# SMPS_Template.net
KiCad netlist of a schematic drawn in Altium Designer
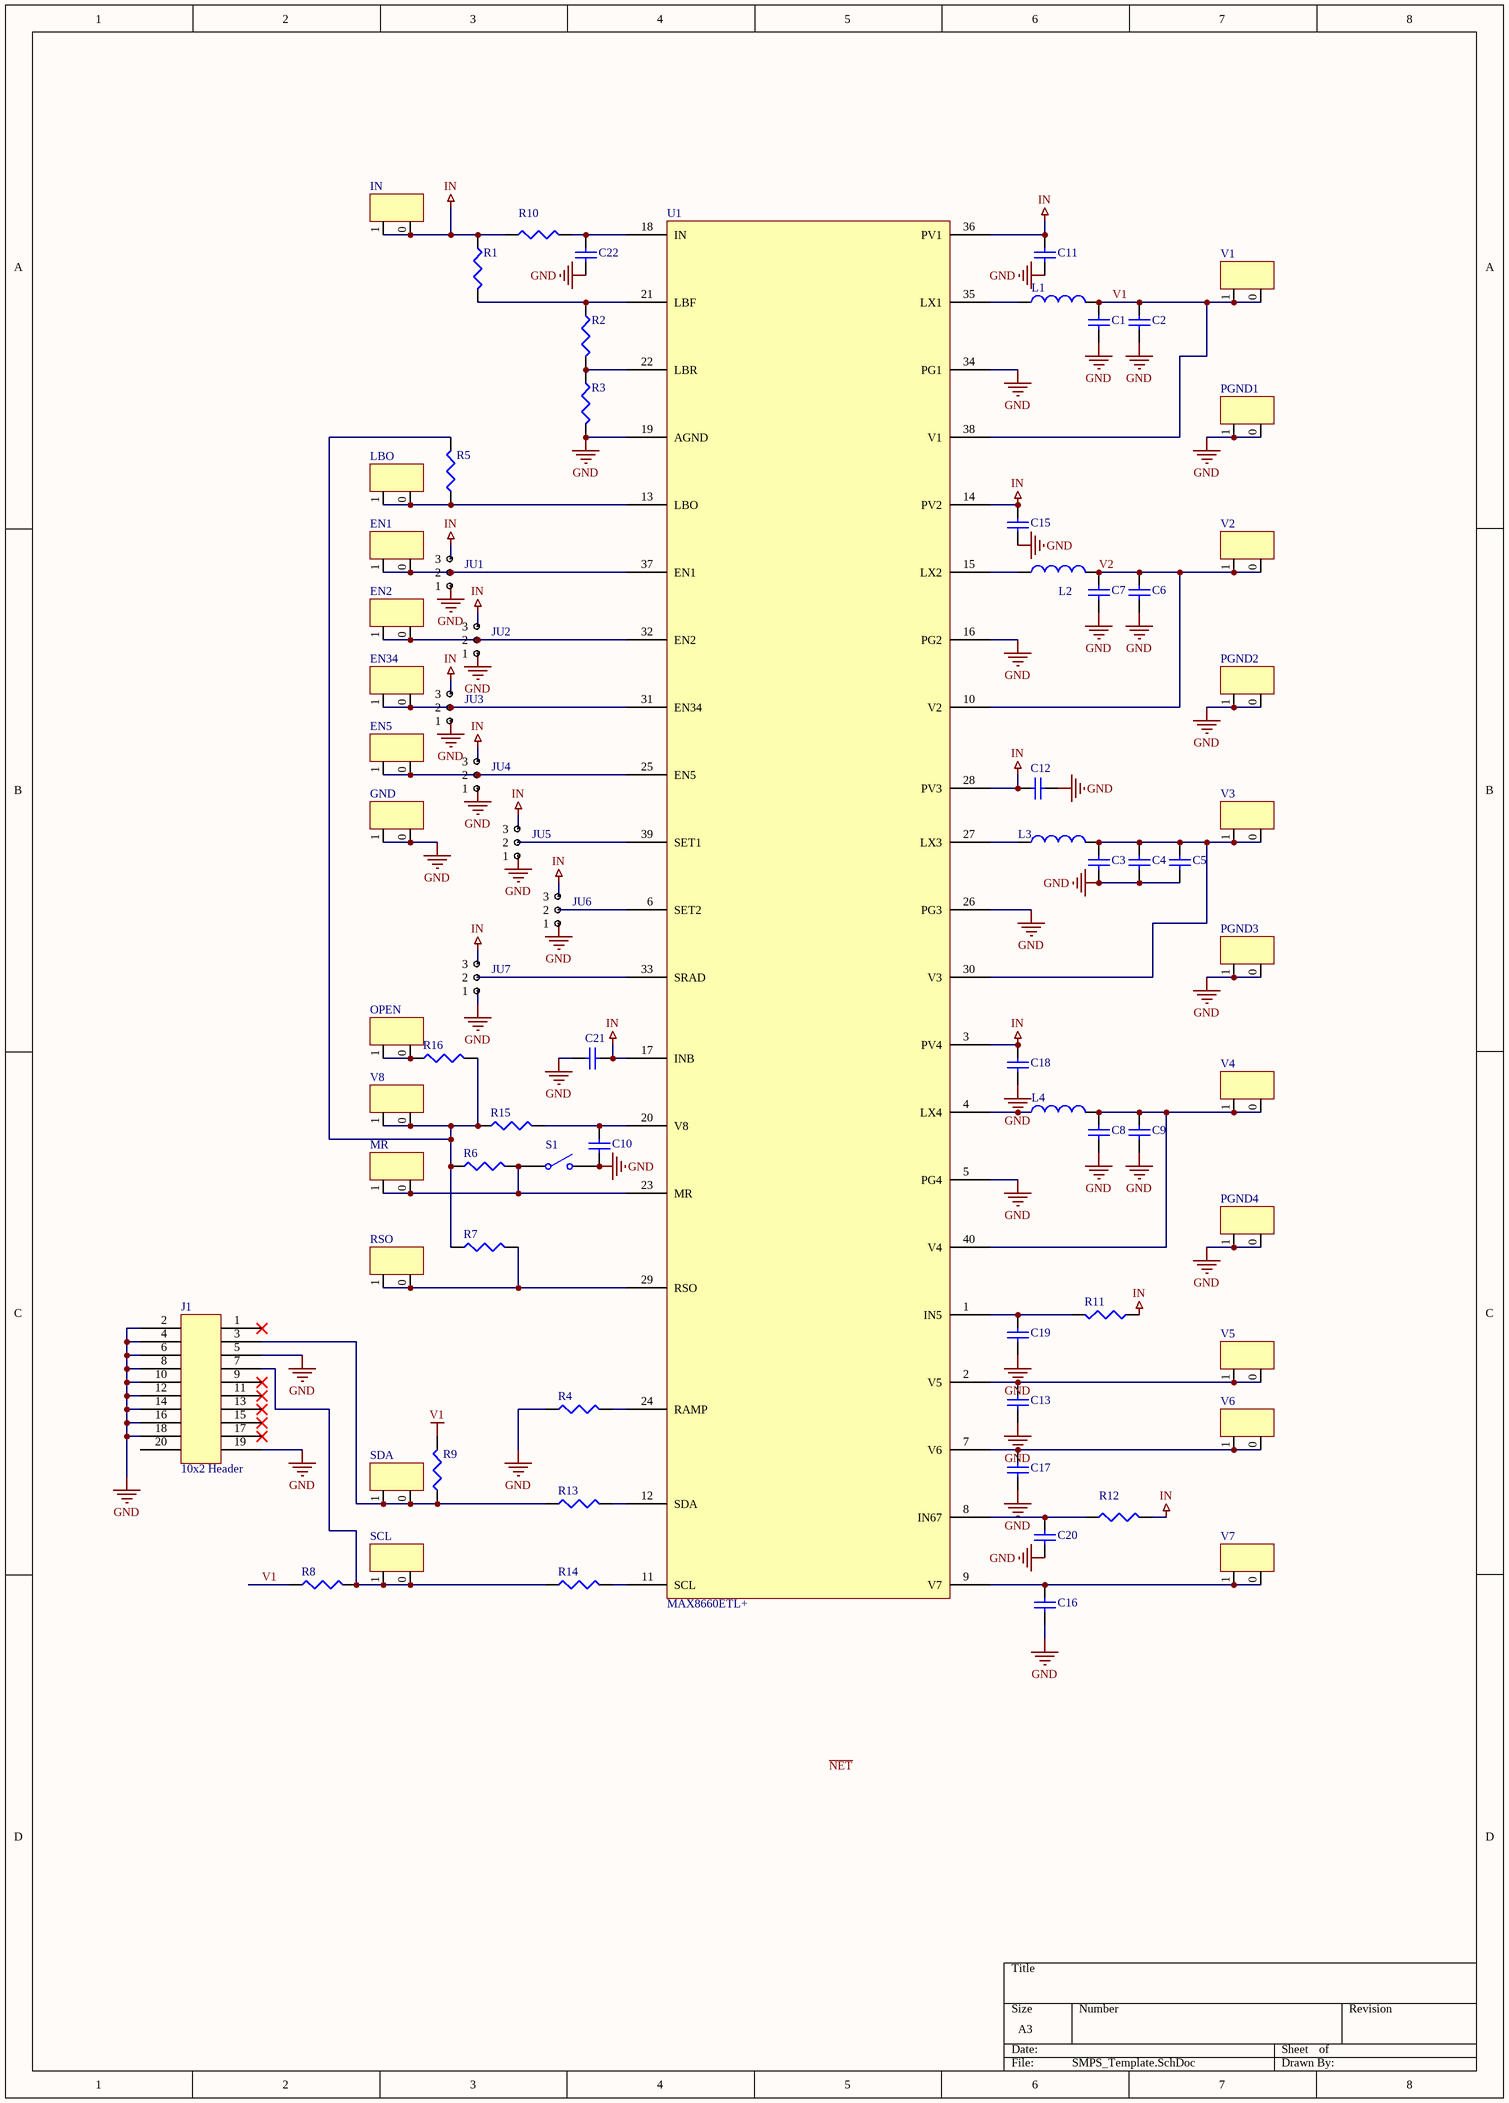
[diagram p0: SMPS_Template.SchDoc]

(export (version "E")
  (design (tool "Eeschema 10.0.6"))
  (components
    (comp (ref "C1")
      (value "Cap")
      (footprint "2012[0805]")
      (description "Capacitor")
      (fields (field (name "PUBLISHER") "Altium Limited"))
      (libsource (lib "Miscellaneous Devices") (part "Cap"))
    )
    (comp (ref "C2")
      (value "Cap")
      (footprint "2012[0805]")
      (description "Capacitor")
      (fields (field (name "PUBLISHER") "Altium Limited"))
      (libsource (lib "Miscellaneous Devices") (part "Cap"))
    )
    (comp (ref "C3")
      (value "Cap")
      (footprint "2012[0805]")
      (description "Capacitor")
      (fields (field (name "PUBLISHER") "Altium Limited"))
      (libsource (lib "Miscellaneous Devices") (part "Cap"))
    )
    (comp (ref "C4")
      (value "Cap")
      (footprint "2012[0805]")
      (description "Capacitor")
      (fields (field (name "PUBLISHER") "Altium Limited"))
      (libsource (lib "Miscellaneous Devices") (part "Cap"))
    )
    (comp (ref "C5")
      (value "Cap")
      (footprint "2012[0805]")
      (description "Capacitor")
      (fields (field (name "PUBLISHER") "Altium Limited"))
      (libsource (lib "Miscellaneous Devices") (part "Cap"))
    )
    (comp (ref "C6")
      (value "Cap")
      (footprint "2012[0805]")
      (description "Capacitor")
      (fields (field (name "PUBLISHER") "Altium Limited"))
      (libsource (lib "Miscellaneous Devices") (part "Cap"))
    )
    (comp (ref "C7")
      (value "Cap")
      (footprint "2012[0805]")
      (description "Capacitor")
      (fields (field (name "PUBLISHER") "Altium Limited"))
      (libsource (lib "Miscellaneous Devices") (part "Cap"))
    )
    (comp (ref "C8")
      (value "Cap")
      (footprint "2012[0805]")
      (description "Capacitor")
      (fields (field (name "PUBLISHER") "Altium Limited"))
      (libsource (lib "Miscellaneous Devices") (part "Cap"))
    )
    (comp (ref "C9")
      (value "Cap")
      (footprint "2012[0805]")
      (description "Capacitor")
      (fields (field (name "PUBLISHER") "Altium Limited"))
      (libsource (lib "Miscellaneous Devices") (part "Cap"))
    )
    (comp (ref "C10")
      (value "Cap")
      (footprint "1005[0402]")
      (description "Capacitor")
      (fields (field (name "PUBLISHER") "Altium Limited"))
      (libsource (lib "Miscellaneous Devices") (part "Cap"))
    )
    (comp (ref "C11")
      (value "Cap")
      (footprint "1608[0603]")
      (description "Capacitor")
      (fields (field (name "PUBLISHER") "Altium Limited"))
      (libsource (lib "Miscellaneous Devices") (part "Cap"))
    )
    (comp (ref "C12")
      (value "Cap")
      (footprint "1608[0603]")
      (description "Capacitor")
      (fields (field (name "PUBLISHER") "Altium Limited"))
      (libsource (lib "Miscellaneous Devices") (part "Cap"))
    )
    (comp (ref "C13")
      (value "Cap")
      (footprint "1608[0603]")
      (description "Capacitor")
      (fields (field (name "PUBLISHER") "Altium Limited"))
      (libsource (lib "Miscellaneous Devices") (part "Cap"))
    )
    (comp (ref "C15")
      (value "Cap")
      (footprint "1608[0603]")
      (description "Capacitor")
      (fields (field (name "PUBLISHER") "Altium Limited"))
      (libsource (lib "Miscellaneous Devices") (part "Cap"))
    )
    (comp (ref "C16")
      (value "Cap")
      (footprint "1608[0603]")
      (description "Capacitor")
      (fields (field (name "PUBLISHER") "Altium Limited"))
      (libsource (lib "Miscellaneous Devices") (part "Cap"))
    )
    (comp (ref "C17")
      (value "Cap")
      (footprint "1608[0603]")
      (description "Capacitor")
      (fields (field (name "PUBLISHER") "Altium Limited"))
      (libsource (lib "Miscellaneous Devices") (part "Cap"))
    )
    (comp (ref "C18")
      (value "Cap")
      (footprint "1608[0603]")
      (description "Capacitor")
      (fields (field (name "PUBLISHER") "Altium Limited"))
      (libsource (lib "Miscellaneous Devices") (part "Cap"))
    )
    (comp (ref "C19")
      (value "Cap")
      (footprint "1608[0603]")
      (description "Capacitor")
      (fields (field (name "PUBLISHER") "Altium Limited"))
      (libsource (lib "Miscellaneous Devices") (part "Cap"))
    )
    (comp (ref "C20")
      (value "Cap")
      (footprint "1608[0603]")
      (description "Capacitor")
      (fields (field (name "PUBLISHER") "Altium Limited"))
      (libsource (lib "Miscellaneous Devices") (part "Cap"))
    )
    (comp (ref "C21")
      (value "Cap")
      (footprint "1005[0402]")
      (description "Capacitor")
      (fields (field (name "PUBLISHER") "Altium Limited"))
      (libsource (lib "Miscellaneous Devices") (part "Cap"))
    )
    (comp (ref "C22")
      (value "Cap")
      (footprint "1005[0402]")
      (description "Capacitor")
      (fields (field (name "PUBLISHER") "Altium Limited"))
      (libsource (lib "Miscellaneous Devices") (part "Cap"))
    )
    (comp (ref "EN1")
      (value "2-pin Header")
      (footprint "CON_1")
      (libsource (lib "Proj_SchLib") (part "2-pin Header"))
    )
    (comp (ref "EN2")
      (value "2-pin Header")
      (footprint "CON_1")
      (libsource (lib "Proj_SchLib") (part "2-pin Header"))
    )
    (comp (ref "EN5")
      (value "2-pin Header")
      (footprint "CON_1")
      (libsource (lib "Proj_SchLib") (part "2-pin Header"))
    )
    (comp (ref "EN34")
      (value "2-pin Header")
      (footprint "CON_1")
      (libsource (lib "Proj_SchLib") (part "2-pin Header"))
    )
    (comp (ref "GND")
      (value "2-pin Header")
      (footprint "CON_1")
      (libsource (lib "Proj_SchLib") (part "2-pin Header"))
    )
    (comp (ref "IN")
      (value "2-pin Header")
      (footprint "CON_1")
      (libsource (lib "Proj_SchLib") (part "2-pin Header"))
    )
    (comp (ref "J1")
      (value "10x2 Header")
      (footprint "HDR2X10")
      (libsource (lib "Proj_SchLib") (part "10x2 Header"))
    )
    (comp (ref "JU1")
      (value "3-pin Header")
      (footprint "CON3")
      (libsource (lib "Proj_SchLib") (part "3-pin Header"))
    )
    (comp (ref "JU2")
      (value "3-pin Header")
      (footprint "CON3")
      (libsource (lib "Proj_SchLib") (part "3-pin Header"))
    )
    (comp (ref "JU3")
      (value "3-pin Header")
      (footprint "CON3")
      (libsource (lib "Proj_SchLib") (part "3-pin Header"))
    )
    (comp (ref "JU4")
      (value "3-pin Header")
      (footprint "CON3")
      (libsource (lib "Proj_SchLib") (part "3-pin Header"))
    )
    (comp (ref "JU5")
      (value "3-pin Header")
      (footprint "CON3")
      (libsource (lib "Proj_SchLib") (part "3-pin Header"))
    )
    (comp (ref "JU6")
      (value "3-pin Header")
      (footprint "CON3")
      (libsource (lib "Proj_SchLib") (part "3-pin Header"))
    )
    (comp (ref "JU7")
      (value "3-pin Header")
      (footprint "CON3")
      (libsource (lib "Proj_SchLib") (part "3-pin Header"))
    )
    (comp (ref "L1")
      (value "Inductor")
      (footprint "INDC3225L")
      (fields (field (name "PUBLISHER") "Altium Limited"))
      (libsource (lib "Miscellaneous Devices") (part "Inductor"))
    )
    (comp (ref "L2")
      (value "Inductor")
      (footprint "INDC3225L")
      (fields (field (name "PUBLISHER") "Altium Limited"))
      (libsource (lib "Miscellaneous Devices") (part "Inductor"))
    )
    (comp (ref "L3")
      (value "Inductor")
      (footprint "INDC3225L")
      (fields (field (name "PUBLISHER") "Altium Limited"))
      (libsource (lib "Miscellaneous Devices") (part "Inductor"))
    )
    (comp (ref "L4")
      (value "Inductor")
      (footprint "INDC3225L")
      (fields (field (name "PUBLISHER") "Altium Limited"))
      (libsource (lib "Miscellaneous Devices") (part "Inductor"))
    )
    (comp (ref "LBO")
      (value "2-pin Header")
      (footprint "CON_1")
      (libsource (lib "Proj_SchLib") (part "2-pin Header"))
    )
    (comp (ref "MR")
      (value "2-pin Header")
      (footprint "CON_1")
      (libsource (lib "Proj_SchLib") (part "2-pin Header"))
    )
    (comp (ref "OPEN")
      (value "2-pin Header")
      (footprint "CON_1")
      (libsource (lib "Proj_SchLib") (part "2-pin Header"))
    )
    (comp (ref "PGND1")
      (value "2-pin Header")
      (footprint "CON_1")
      (libsource (lib "Proj_SchLib") (part "2-pin Header"))
    )
    (comp (ref "PGND2")
      (value "2-pin Header")
      (footprint "CON_1")
      (libsource (lib "Proj_SchLib") (part "2-pin Header"))
    )
    (comp (ref "PGND3")
      (value "2-pin Header")
      (footprint "CON_1")
      (libsource (lib "Proj_SchLib") (part "2-pin Header"))
    )
    (comp (ref "PGND4")
      (value "2-pin Header")
      (footprint "CON_1")
      (libsource (lib "Proj_SchLib") (part "2-pin Header"))
    )
    (comp (ref "R1")
      (value "Res3")
      (footprint "1005[0402]")
      (description "Resistor")
      (fields (field (name "PUBLISHER") "Altium Limited"))
      (libsource (lib "Miscellaneous Devices") (part "Res3"))
    )
    (comp (ref "R2")
      (value "Res3")
      (footprint "1005[0402]")
      (description "Resistor")
      (fields (field (name "PUBLISHER") "Altium Limited"))
      (libsource (lib "Miscellaneous Devices") (part "Res3"))
    )
    (comp (ref "R3")
      (value "Res3")
      (footprint "1005[0402]")
      (description "Resistor")
      (fields (field (name "PUBLISHER") "Altium Limited"))
      (libsource (lib "Miscellaneous Devices") (part "Res3"))
    )
    (comp (ref "R4")
      (value "Res3")
      (footprint "1005[0402]")
      (description "Resistor")
      (fields (field (name "PUBLISHER") "Altium Limited"))
      (libsource (lib "Miscellaneous Devices") (part "Res3"))
    )
    (comp (ref "R5")
      (value "Res3")
      (footprint "2012[0805]")
      (description "Resistor")
      (fields (field (name "PUBLISHER") "Altium Limited"))
      (libsource (lib "Miscellaneous Devices") (part "Res3"))
    )
    (comp (ref "R6")
      (value "Res3")
      (footprint "2012[0805]")
      (description "Resistor")
      (fields (field (name "PUBLISHER") "Altium Limited"))
      (libsource (lib "Miscellaneous Devices") (part "Res3"))
    )
    (comp (ref "R7")
      (value "Res3")
      (footprint "2012[0805]")
      (description "Resistor")
      (fields (field (name "PUBLISHER") "Altium Limited"))
      (libsource (lib "Miscellaneous Devices") (part "Res3"))
    )
    (comp (ref "R8")
      (value "Res3")
      (footprint "2012[0805]")
      (description "Resistor")
      (fields (field (name "PUBLISHER") "Altium Limited"))
      (libsource (lib "Miscellaneous Devices") (part "Res3"))
    )
    (comp (ref "R9")
      (value "Res3")
      (footprint "2012[0805]")
      (description "Resistor")
      (fields (field (name "PUBLISHER") "Altium Limited"))
      (libsource (lib "Miscellaneous Devices") (part "Res3"))
    )
    (comp (ref "R10")
      (value "20 Ohm")
      (footprint "1005[0402]")
      (description "Resistor")
      (fields (field (name "PUBLISHER") "Altium Limited"))
      (libsource (lib "Miscellaneous Devices") (part "Res3"))
    )
    (comp (ref "R11")
      (value "Res3")
      (footprint "1005[0402]")
      (description "Resistor")
      (fields (field (name "PUBLISHER") "Altium Limited"))
      (libsource (lib "Miscellaneous Devices") (part "Res3"))
    )
    (comp (ref "R12")
      (value "Res3")
      (footprint "1005[0402]")
      (description "Resistor")
      (fields (field (name "PUBLISHER") "Altium Limited"))
      (libsource (lib "Miscellaneous Devices") (part "Res3"))
    )
    (comp (ref "R13")
      (value "Res3")
      (footprint "2012[0805]")
      (description "Resistor")
      (fields (field (name "PUBLISHER") "Altium Limited"))
      (libsource (lib "Miscellaneous Devices") (part "Res3"))
    )
    (comp (ref "R14")
      (value "Res3")
      (footprint "2012[0805]")
      (description "Resistor")
      (fields (field (name "PUBLISHER") "Altium Limited"))
      (libsource (lib "Miscellaneous Devices") (part "Res3"))
    )
    (comp (ref "R15")
      (value "SHORT")
      (footprint "2012[0805]")
      (description "Resistor")
      (fields (field (name "PUBLISHER") "Altium Limited"))
      (libsource (lib "Miscellaneous Devices") (part "Res3"))
    )
    (comp (ref "R16")
      (value "OPEN")
      (footprint "2012[0805]")
      (description "Resistor")
      (fields (field (name "PUBLISHER") "Altium Limited"))
      (libsource (lib "Miscellaneous Devices") (part "Res3"))
    )
    (comp (ref "RSO")
      (value "2-pin Header")
      (footprint "CON_1")
      (libsource (lib "Proj_SchLib") (part "2-pin Header"))
    )
    (comp (ref "S1")
      (value "SW-SPST")
      (footprint "PUSH_SWITCH")
      (description "Single-Pole, Single-Throw Switch")
      (fields (field (name "PUBLISHER") "Altium Limited"))
      (libsource (lib "Miscellaneous Devices") (part "SW-SPST"))
    )
    (comp (ref "SCL")
      (value "2-pin Header")
      (footprint "CON_1")
      (libsource (lib "Proj_SchLib") (part "2-pin Header"))
    )
    (comp (ref "SDA")
      (value "2-pin Header")
      (footprint "CON_1")
      (libsource (lib "Proj_SchLib") (part "2-pin Header"))
    )
    (comp (ref "U1")
      (value "MAX8660ETL+")
      (footprint "MAX8660_QFN")
      (libsource (lib "Proj_SchLib") (part "MAX8660ETL+"))
    )
    (comp (ref "V1")
      (value "2-pin Header")
      (footprint "CON_1")
      (libsource (lib "Proj_SchLib") (part "2-pin Header"))
    )
    (comp (ref "V2")
      (value "2-pin Header")
      (footprint "CON_1")
      (libsource (lib "Proj_SchLib") (part "2-pin Header"))
    )
    (comp (ref "V3")
      (value "2-pin Header")
      (footprint "CON_1")
      (libsource (lib "Proj_SchLib") (part "2-pin Header"))
    )
    (comp (ref "V4")
      (value "2-pin Header")
      (footprint "CON_1")
      (libsource (lib "Proj_SchLib") (part "2-pin Header"))
    )
    (comp (ref "V5")
      (value "2-pin Header")
      (footprint "CON_1")
      (libsource (lib "Proj_SchLib") (part "2-pin Header"))
    )
    (comp (ref "V6")
      (value "2-pin Header")
      (footprint "CON_1")
      (libsource (lib "Proj_SchLib") (part "2-pin Header"))
    )
    (comp (ref "V7")
      (value "2-pin Header")
      (footprint "CON_1")
      (libsource (lib "Proj_SchLib") (part "2-pin Header"))
    )
    (comp (ref "V8")
      (value "2-pin Header")
      (footprint "CON_1")
      (libsource (lib "Proj_SchLib") (part "2-pin Header"))
    )
  )
  (nets
    (net (code "1") (name "/V2") (class "Default")
      (node (ref "C6") (pin "2") (pinfunction "2_2") (pintype "passive"))
      (node (ref "C7") (pin "2") (pinfunction "2_2") (pintype "passive"))
      (node (ref "L2") (pin "2") (pinfunction "2_2") (pintype "passive"))
      (node (ref "U1") (pin "10") (pinfunction "V2_10") (pintype "passive"))
      (node (ref "V2") (pin "0") (pinfunction "0_0") (pintype "passive"))
      (node (ref "V2") (pin "1") (pinfunction "1_1") (pintype "passive"))
    )
    (net (code "3") (name "GND") (class "Default")
      (node (ref "C1") (pin "1") (pinfunction "1_1") (pintype "passive"))
      (node (ref "C10") (pin "2") (pinfunction "2_2") (pintype "passive"))
      (node (ref "C11") (pin "1") (pinfunction "1_1") (pintype "passive"))
      (node (ref "C12") (pin "1") (pinfunction "1_1") (pintype "passive"))
      (node (ref "C13") (pin "1") (pinfunction "1_1") (pintype "passive"))
      (node (ref "C15") (pin "1") (pinfunction "1_1") (pintype "passive"))
      (node (ref "C16") (pin "1") (pinfunction "1_1") (pintype "passive"))
      (node (ref "C17") (pin "1") (pinfunction "1_1") (pintype "passive"))
      (node (ref "C18") (pin "1") (pinfunction "1_1") (pintype "passive"))
      (node (ref "C19") (pin "1") (pinfunction "1_1") (pintype "passive"))
      (node (ref "C2") (pin "1") (pinfunction "1_1") (pintype "passive"))
      (node (ref "C20") (pin "1") (pinfunction "1_1") (pintype "passive"))
      (node (ref "C21") (pin "2") (pinfunction "2_2") (pintype "passive"))
      (node (ref "C22") (pin "1") (pinfunction "1_1") (pintype "passive"))
      (node (ref "C3") (pin "1") (pinfunction "1_1") (pintype "passive"))
      (node (ref "C4") (pin "1") (pinfunction "1_1") (pintype "passive"))
      (node (ref "C5") (pin "1") (pinfunction "1_1") (pintype "passive"))
      (node (ref "C6") (pin "1") (pinfunction "1_1") (pintype "passive"))
      (node (ref "C7") (pin "1") (pinfunction "1_1") (pintype "passive"))
      (node (ref "C8") (pin "1") (pinfunction "1_1") (pintype "passive"))
      (node (ref "C9") (pin "1") (pinfunction "1_1") (pintype "passive"))
      (node (ref "GND") (pin "0") (pinfunction "0_0") (pintype "passive"))
      (node (ref "GND") (pin "1") (pinfunction "1_1") (pintype "passive"))
      (node (ref "J1") (pin "10") (pinfunction "9_10") (pintype "passive"))
      (node (ref "J1") (pin "12") (pinfunction "11_12") (pintype "passive"))
      (node (ref "J1") (pin "14") (pinfunction "13_14") (pintype "passive"))
      (node (ref "J1") (pin "16") (pinfunction "15_16") (pintype "passive"))
      (node (ref "J1") (pin "18") (pinfunction "17_18") (pintype "passive"))
      (node (ref "J1") (pin "19") (pinfunction "18_19") (pintype "passive"))
      (node (ref "J1") (pin "2") (pinfunction "1_2") (pintype "passive"))
      (node (ref "J1") (pin "4") (pinfunction "3_4") (pintype "passive"))
      (node (ref "J1") (pin "5") (pinfunction "4_5") (pintype "passive"))
      (node (ref "J1") (pin "6") (pinfunction "5_6") (pintype "passive"))
      (node (ref "J1") (pin "8") (pinfunction "7_8") (pintype "passive"))
      (node (ref "JU1") (pin "1") (pinfunction "1_1") (pintype "passive"))
      (node (ref "JU2") (pin "1") (pinfunction "1_1") (pintype "passive"))
      (node (ref "JU3") (pin "1") (pinfunction "1_1") (pintype "passive"))
      (node (ref "JU4") (pin "1") (pinfunction "1_1") (pintype "passive"))
      (node (ref "JU5") (pin "1") (pinfunction "1_1") (pintype "passive"))
      (node (ref "JU6") (pin "1") (pinfunction "1_1") (pintype "passive"))
      (node (ref "JU7") (pin "1") (pinfunction "1_1") (pintype "passive"))
      (node (ref "PGND1") (pin "0") (pinfunction "0_0") (pintype "passive"))
      (node (ref "PGND1") (pin "1") (pinfunction "1_1") (pintype "passive"))
      (node (ref "PGND2") (pin "0") (pinfunction "0_0") (pintype "passive"))
      (node (ref "PGND2") (pin "1") (pinfunction "1_1") (pintype "passive"))
      (node (ref "PGND3") (pin "0") (pinfunction "0_0") (pintype "passive"))
      (node (ref "PGND3") (pin "1") (pinfunction "1_1") (pintype "passive"))
      (node (ref "PGND4") (pin "0") (pinfunction "0_0") (pintype "passive"))
      (node (ref "PGND4") (pin "1") (pinfunction "1_1") (pintype "passive"))
      (node (ref "R3") (pin "2") (pinfunction "2_2") (pintype "passive"))
      (node (ref "R4") (pin "1") (pinfunction "1_1") (pintype "passive"))
      (node (ref "S1") (pin "2") (pinfunction "NO_2") (pintype "passive"))
      (node (ref "U1") (pin "16") (pinfunction "PG2_16") (pintype "passive"))
      (node (ref "U1") (pin "19") (pinfunction "AGND_19") (pintype "passive"))
      (node (ref "U1") (pin "26") (pinfunction "PG3_26") (pintype "passive"))
      (node (ref "U1") (pin "34") (pinfunction "PG1_34") (pintype "passive"))
      (node (ref "U1") (pin "5") (pinfunction "PG4_5") (pintype "passive"))
    )
    (net (code "4") (name "IN") (class "Default")
      (node (ref "C11") (pin "2") (pinfunction "2_2") (pintype "passive"))
      (node (ref "C12") (pin "2") (pinfunction "2_2") (pintype "passive"))
      (node (ref "C15") (pin "2") (pinfunction "2_2") (pintype "passive"))
      (node (ref "C18") (pin "2") (pinfunction "2_2") (pintype "passive"))
      (node (ref "C21") (pin "1") (pinfunction "1_1") (pintype "passive"))
      (node (ref "IN") (pin "0") (pinfunction "0_0") (pintype "passive"))
      (node (ref "IN") (pin "1") (pinfunction "1_1") (pintype "passive"))
      (node (ref "JU1") (pin "3") (pinfunction "3_3") (pintype "passive"))
      (node (ref "JU2") (pin "3") (pinfunction "3_3") (pintype "passive"))
      (node (ref "JU3") (pin "3") (pinfunction "3_3") (pintype "passive"))
      (node (ref "JU4") (pin "3") (pinfunction "3_3") (pintype "passive"))
      (node (ref "JU5") (pin "3") (pinfunction "3_3") (pintype "passive"))
      (node (ref "JU6") (pin "3") (pinfunction "3_3") (pintype "passive"))
      (node (ref "JU7") (pin "3") (pinfunction "3_3") (pintype "passive"))
      (node (ref "R1") (pin "1") (pinfunction "1_1") (pintype "passive"))
      (node (ref "R10") (pin "1") (pinfunction "1_1") (pintype "passive"))
      (node (ref "R11") (pin "1") (pinfunction "1_1") (pintype "passive"))
      (node (ref "R12") (pin "2") (pinfunction "2_2") (pintype "passive"))
      (node (ref "U1") (pin "14") (pinfunction "PV2_14") (pintype "passive"))
      (node (ref "U1") (pin "17") (pinfunction "INB_17") (pintype "passive"))
      (node (ref "U1") (pin "28") (pinfunction "PV3_28") (pintype "passive"))
      (node (ref "U1") (pin "3") (pinfunction "PV4_3") (pintype "passive"))
      (node (ref "U1") (pin "36") (pinfunction "PV1_36") (pintype "passive"))
    )
    (net (code "5") (name "Net-(J1-2)") (class "Default")
      (node (ref "J1") (pin "3") (pinfunction "2_3") (pintype "passive"))
      (node (ref "R13") (pin "1") (pinfunction "1_1") (pintype "passive"))
      (node (ref "R9") (pin "1") (pinfunction "1_1") (pintype "passive"))
      (node (ref "SDA") (pin "0") (pinfunction "0_0") (pintype "passive"))
      (node (ref "SDA") (pin "1") (pinfunction "1_1") (pintype "passive"))
    )
    (net (code "6") (name "Net-(J1-6)") (class "Default")
      (node (ref "J1") (pin "7") (pinfunction "6_7") (pintype "passive"))
      (node (ref "R14") (pin "1") (pinfunction "1_1") (pintype "passive"))
      (node (ref "R8") (pin "2") (pinfunction "2_2") (pintype "passive"))
      (node (ref "SCL") (pin "0") (pinfunction "0_0") (pintype "passive"))
      (node (ref "SCL") (pin "1") (pinfunction "1_1") (pintype "passive"))
    )
    (net (code "7") (name "Net-(OPEN-Pad0)") (class "Default")
      (node (ref "OPEN") (pin "0") (pinfunction "0_0") (pintype "passive"))
      (node (ref "OPEN") (pin "1") (pinfunction "1_1") (pintype "passive"))
      (node (ref "R16") (pin "1") (pinfunction "1_1") (pintype "passive"))
    )
    (net (code "8") (name "Net-(R15-Pad1)") (class "Default")
      (node (ref "R15") (pin "1") (pinfunction "1_1") (pintype "passive"))
      (node (ref "R16") (pin "2") (pinfunction "2_2") (pintype "passive"))
      (node (ref "R5") (pin "2") (pinfunction "2_2") (pintype "passive"))
      (node (ref "R6") (pin "1") (pinfunction "1_1") (pintype "passive"))
      (node (ref "R7") (pin "1") (pinfunction "1_1") (pintype "passive"))
      (node (ref "V8") (pin "0") (pinfunction "0_0") (pintype "passive"))
      (node (ref "V8") (pin "1") (pinfunction "1_1") (pintype "passive"))
    )
    (net (code "9") (name "Net-(S1-COMMON)") (class "Default")
      (node (ref "MR") (pin "0") (pinfunction "0_0") (pintype "passive"))
      (node (ref "MR") (pin "1") (pinfunction "1_1") (pintype "passive"))
      (node (ref "R6") (pin "2") (pinfunction "2_2") (pintype "passive"))
      (node (ref "S1") (pin "1") (pinfunction "COMMON_1") (pintype "passive"))
      (node (ref "U1") (pin "23") (pinfunction "MR_23") (pintype "passive"))
    )
    (net (code "10") (name "Net-(U1-EN1)") (class "Default")
      (node (ref "EN1") (pin "0") (pinfunction "0_0") (pintype "passive"))
      (node (ref "EN1") (pin "1") (pinfunction "1_1") (pintype "passive"))
      (node (ref "JU1") (pin "2") (pinfunction "2_2") (pintype "passive"))
      (node (ref "U1") (pin "37") (pinfunction "EN1_37") (pintype "passive"))
    )
    (net (code "11") (name "Net-(U1-EN2)") (class "Default")
      (node (ref "EN2") (pin "0") (pinfunction "0_0") (pintype "passive"))
      (node (ref "EN2") (pin "1") (pinfunction "1_1") (pintype "passive"))
      (node (ref "JU2") (pin "2") (pinfunction "2_2") (pintype "passive"))
      (node (ref "U1") (pin "32") (pinfunction "EN2_32") (pintype "passive"))
    )
    (net (code "12") (name "Net-(U1-EN5)") (class "Default")
      (node (ref "EN5") (pin "0") (pinfunction "0_0") (pintype "passive"))
      (node (ref "EN5") (pin "1") (pinfunction "1_1") (pintype "passive"))
      (node (ref "JU4") (pin "2") (pinfunction "2_2") (pintype "passive"))
      (node (ref "U1") (pin "25") (pinfunction "EN5_25") (pintype "passive"))
    )
    (net (code "13") (name "Net-(U1-EN34)") (class "Default")
      (node (ref "EN34") (pin "0") (pinfunction "0_0") (pintype "passive"))
      (node (ref "EN34") (pin "1") (pinfunction "1_1") (pintype "passive"))
      (node (ref "JU3") (pin "2") (pinfunction "2_2") (pintype "passive"))
      (node (ref "U1") (pin "31") (pinfunction "EN34_31") (pintype "passive"))
    )
    (net (code "14") (name "Net-(U1-IN)") (class "Default")
      (node (ref "C22") (pin "2") (pinfunction "2_2") (pintype "passive"))
      (node (ref "R10") (pin "2") (pinfunction "2_2") (pintype "passive"))
      (node (ref "U1") (pin "18") (pinfunction "IN_18") (pintype "passive"))
    )
    (net (code "15") (name "Net-(U1-IN5)") (class "Default")
      (node (ref "C19") (pin "2") (pinfunction "2_2") (pintype "passive"))
      (node (ref "R11") (pin "2") (pinfunction "2_2") (pintype "passive"))
      (node (ref "U1") (pin "1") (pinfunction "IN5_1") (pintype "passive"))
    )
    (net (code "16") (name "Net-(U1-IN67)") (class "Default")
      (node (ref "C20") (pin "2") (pinfunction "2_2") (pintype "passive"))
      (node (ref "R12") (pin "1") (pinfunction "1_1") (pintype "passive"))
      (node (ref "U1") (pin "8") (pinfunction "IN67_8") (pintype "passive"))
    )
    (net (code "17") (name "Net-(U1-LBF)") (class "Default")
      (node (ref "R1") (pin "2") (pinfunction "2_2") (pintype "passive"))
      (node (ref "R2") (pin "1") (pinfunction "1_1") (pintype "passive"))
      (node (ref "U1") (pin "21") (pinfunction "LBF_21") (pintype "passive"))
    )
    (net (code "18") (name "Net-(U1-LBO)") (class "Default")
      (node (ref "LBO") (pin "0") (pinfunction "0_0") (pintype "passive"))
      (node (ref "LBO") (pin "1") (pinfunction "1_1") (pintype "passive"))
      (node (ref "R5") (pin "1") (pinfunction "1_1") (pintype "passive"))
      (node (ref "U1") (pin "13") (pinfunction "LBO_13") (pintype "passive"))
    )
    (net (code "19") (name "Net-(U1-LBR)") (class "Default")
      (node (ref "R2") (pin "2") (pinfunction "2_2") (pintype "passive"))
      (node (ref "R3") (pin "1") (pinfunction "1_1") (pintype "passive"))
      (node (ref "U1") (pin "22") (pinfunction "LBR_22") (pintype "passive"))
    )
    (net (code "20") (name "Net-(U1-LX1)") (class "Default")
      (node (ref "L1") (pin "1") (pinfunction "1_1") (pintype "passive"))
      (node (ref "U1") (pin "35") (pinfunction "LX1_35") (pintype "passive"))
    )
    (net (code "21") (name "Net-(U1-LX2)") (class "Default")
      (node (ref "L2") (pin "1") (pinfunction "1_1") (pintype "passive"))
      (node (ref "U1") (pin "15") (pinfunction "LX2_15") (pintype "passive"))
    )
    (net (code "22") (name "Net-(U1-LX3)") (class "Default")
      (node (ref "L3") (pin "1") (pinfunction "1_1") (pintype "passive"))
      (node (ref "U1") (pin "27") (pinfunction "LX3_27") (pintype "passive"))
    )
    (net (code "23") (name "Net-(U1-LX4)") (class "Default")
      (node (ref "L4") (pin "1") (pinfunction "1_1") (pintype "passive"))
      (node (ref "U1") (pin "4") (pinfunction "LX4_4") (pintype "passive"))
    )
    (net (code "24") (name "Net-(U1-RAMP)") (class "Default")
      (node (ref "R4") (pin "2") (pinfunction "2_2") (pintype "passive"))
      (node (ref "U1") (pin "24") (pinfunction "RAMP_24") (pintype "passive"))
    )
    (net (code "25") (name "Net-(U1-RSO)") (class "Default")
      (node (ref "R7") (pin "2") (pinfunction "2_2") (pintype "passive"))
      (node (ref "RSO") (pin "0") (pinfunction "0_0") (pintype "passive"))
      (node (ref "RSO") (pin "1") (pinfunction "1_1") (pintype "passive"))
      (node (ref "U1") (pin "29") (pinfunction "RSO_29") (pintype "passive"))
    )
    (net (code "26") (name "Net-(U1-SCL)") (class "Default")
      (node (ref "R14") (pin "2") (pinfunction "2_2") (pintype "passive"))
      (node (ref "U1") (pin "11") (pinfunction "SCL_11") (pintype "passive"))
    )
    (net (code "27") (name "Net-(U1-SDA)") (class "Default")
      (node (ref "R13") (pin "2") (pinfunction "2_2") (pintype "passive"))
      (node (ref "U1") (pin "12") (pinfunction "SDA_12") (pintype "passive"))
    )
    (net (code "28") (name "Net-(U1-SET1)") (class "Default")
      (node (ref "JU5") (pin "2") (pinfunction "2_2") (pintype "passive"))
      (node (ref "U1") (pin "39") (pinfunction "SET1_39") (pintype "passive"))
    )
    (net (code "29") (name "Net-(U1-SET2)") (class "Default")
      (node (ref "JU6") (pin "2") (pinfunction "2_2") (pintype "passive"))
      (node (ref "U1") (pin "6") (pinfunction "SET2_6") (pintype "passive"))
    )
    (net (code "30") (name "Net-(U1-SRAD)") (class "Default")
      (node (ref "JU7") (pin "2") (pinfunction "2_2") (pintype "passive"))
      (node (ref "U1") (pin "33") (pinfunction "SRAD_33") (pintype "passive"))
    )
    (net (code "31") (name "Net-(U1-V3)") (class "Default")
      (node (ref "C3") (pin "2") (pinfunction "2_2") (pintype "passive"))
      (node (ref "C4") (pin "2") (pinfunction "2_2") (pintype "passive"))
      (node (ref "C5") (pin "2") (pinfunction "2_2") (pintype "passive"))
      (node (ref "L3") (pin "2") (pinfunction "2_2") (pintype "passive"))
      (node (ref "U1") (pin "30") (pinfunction "V3_30") (pintype "passive"))
      (node (ref "V3") (pin "0") (pinfunction "0_0") (pintype "passive"))
      (node (ref "V3") (pin "1") (pinfunction "1_1") (pintype "passive"))
    )
    (net (code "32") (name "Net-(U1-V4)") (class "Default")
      (node (ref "C8") (pin "2") (pinfunction "2_2") (pintype "passive"))
      (node (ref "C9") (pin "2") (pinfunction "2_2") (pintype "passive"))
      (node (ref "L4") (pin "2") (pinfunction "2_2") (pintype "passive"))
      (node (ref "U1") (pin "40") (pinfunction "V4_40") (pintype "passive"))
      (node (ref "V4") (pin "0") (pinfunction "0_0") (pintype "passive"))
      (node (ref "V4") (pin "1") (pinfunction "1_1") (pintype "passive"))
    )
    (net (code "33") (name "Net-(U1-V5)") (class "Default")
      (node (ref "C13") (pin "2") (pinfunction "2_2") (pintype "passive"))
      (node (ref "U1") (pin "2") (pinfunction "V5_2") (pintype "passive"))
      (node (ref "V5") (pin "0") (pinfunction "0_0") (pintype "passive"))
      (node (ref "V5") (pin "1") (pinfunction "1_1") (pintype "passive"))
    )
    (net (code "34") (name "Net-(U1-V6)") (class "Default")
      (node (ref "C17") (pin "2") (pinfunction "2_2") (pintype "passive"))
      (node (ref "U1") (pin "7") (pinfunction "V6_7") (pintype "passive"))
      (node (ref "V6") (pin "0") (pinfunction "0_0") (pintype "passive"))
      (node (ref "V6") (pin "1") (pinfunction "1_1") (pintype "passive"))
    )
    (net (code "35") (name "Net-(U1-V7)") (class "Default")
      (node (ref "C16") (pin "2") (pinfunction "2_2") (pintype "passive"))
      (node (ref "U1") (pin "9") (pinfunction "V7_9") (pintype "passive"))
      (node (ref "V7") (pin "0") (pinfunction "0_0") (pintype "passive"))
      (node (ref "V7") (pin "1") (pinfunction "1_1") (pintype "passive"))
    )
    (net (code "36") (name "Net-(U1-V8)") (class "Default")
      (node (ref "C10") (pin "1") (pinfunction "1_1") (pintype "passive"))
      (node (ref "R15") (pin "2") (pinfunction "2_2") (pintype "passive"))
      (node (ref "U1") (pin "20") (pinfunction "V8_20") (pintype "passive"))
    )
    (net (code "37") (name "V1") (class "Default")
      (node (ref "C1") (pin "2") (pinfunction "2_2") (pintype "passive"))
      (node (ref "C2") (pin "2") (pinfunction "2_2") (pintype "passive"))
      (node (ref "L1") (pin "2") (pinfunction "2_2") (pintype "passive"))
      (node (ref "R8") (pin "1") (pinfunction "1_1") (pintype "passive"))
      (node (ref "R9") (pin "2") (pinfunction "2_2") (pintype "passive"))
      (node (ref "U1") (pin "38") (pinfunction "V1_38") (pintype "passive"))
      (node (ref "V1") (pin "0") (pinfunction "0_0") (pintype "passive"))
      (node (ref "V1") (pin "1") (pinfunction "1_1") (pintype "passive"))
    )
    (net (code "38") (name "unconnected-(J1-0-Pad1)") (class "Default")
      (node (ref "J1") (pin "1") (pinfunction "0_1") (pintype "passive+no_connect"))
    )
    (net (code "39") (name "unconnected-(J1-8-Pad9)") (class "Default")
      (node (ref "J1") (pin "9") (pinfunction "8_9") (pintype "passive+no_connect"))
    )
    (net (code "40") (name "unconnected-(J1-10-Pad11)") (class "Default")
      (node (ref "J1") (pin "11") (pinfunction "10_11") (pintype "passive+no_connect"))
    )
    (net (code "41") (name "unconnected-(J1-12-Pad13)") (class "Default")
      (node (ref "J1") (pin "13") (pinfunction "12_13") (pintype "passive+no_connect"))
    )
    (net (code "42") (name "unconnected-(J1-14-Pad15)") (class "Default")
      (node (ref "J1") (pin "15") (pinfunction "14_15") (pintype "passive+no_connect"))
    )
    (net (code "43") (name "unconnected-(J1-16-Pad17)") (class "Default")
      (node (ref "J1") (pin "17") (pinfunction "16_17") (pintype "passive+no_connect"))
    )
    (net (code "44") (name "unconnected-(J1-19-Pad20)") (class "Default")
      (node (ref "J1") (pin "20") (pinfunction "19_20") (pintype "passive"))
    )
  )
)
